# Maduino_Zero_Lorawan_Node_v2_0.net
KiCad netlist of a schematic drawn in EAGLE
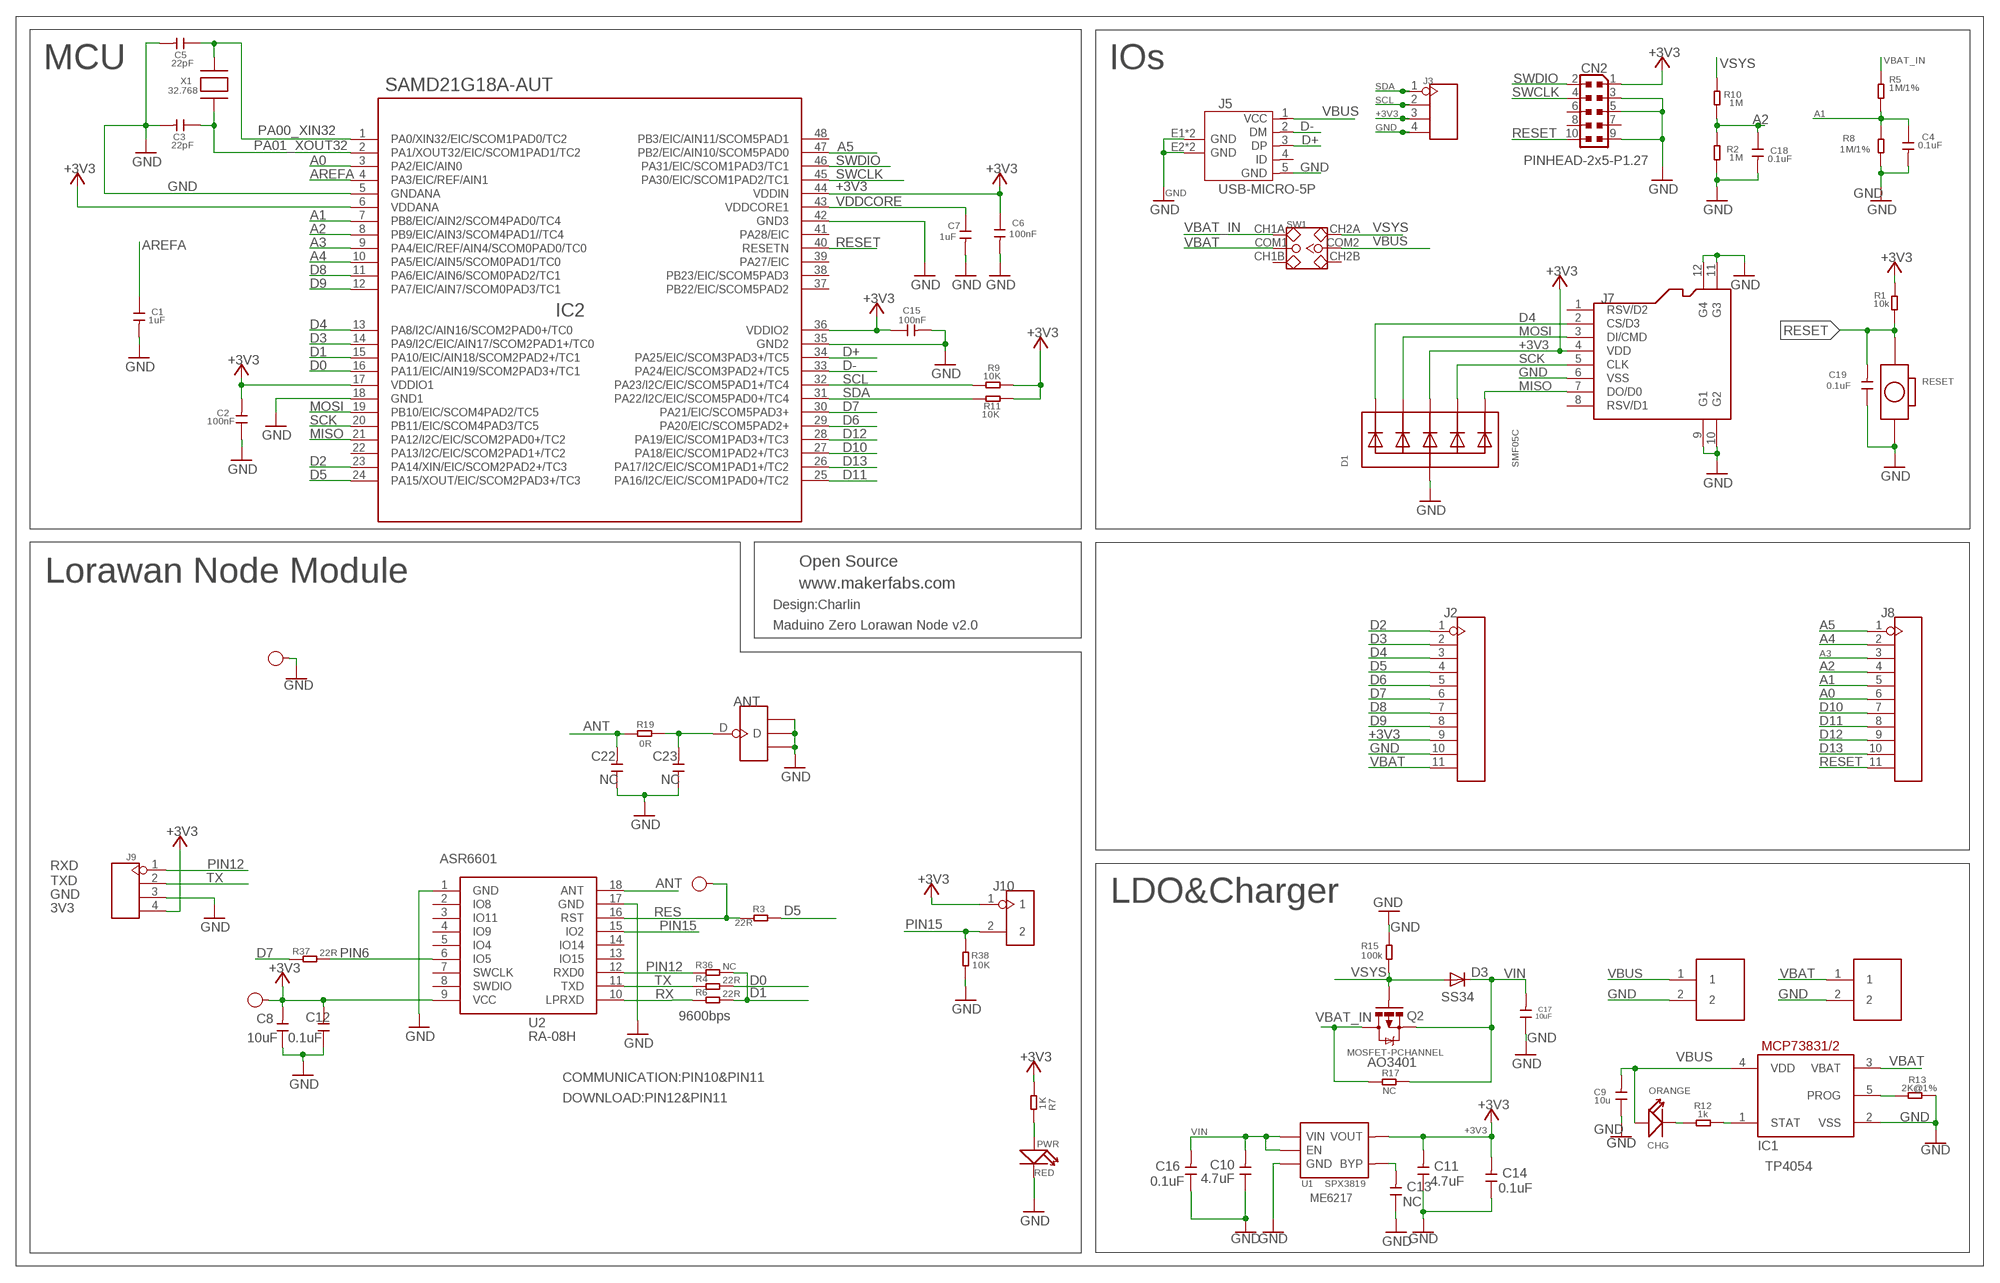
[diagram p0: schematic, sheet 1]

(export (version "E")
  (design (tool "Eeschema 10.0.6"))
  (components
    (comp (ref "3V3")
      (value "TEST-POINT'4545'")
      (footprint "eagle-import:TP-D45MIL")
      (fields (field (name "PARTNO") "DNP") (field (name "PARTNO_1") "DNP"))
      (libsource (lib "eagle-import") (part "TEST-POINT'4545'"))
    )
    (comp (ref "ANT")
      (value "ANTENNA-U-FL")
      (footprint "eagle-import:4P-U-FL")
      (libsource (lib "eagle-import") (part "ANTENNA-U-FL"))
    )
    (comp (ref "C1")
      (value "1uF")
      (footprint "eagle-import:0603")
      (libsource (lib "eagle-import") (part "C-0603"))
    )
    (comp (ref "C2")
      (value "100nF")
      (footprint "eagle-import:0603")
      (libsource (lib "eagle-import") (part "C-0603"))
    )
    (comp (ref "C3")
      (value "22pF")
      (footprint "eagle-import:0603")
      (libsource (lib "eagle-import") (part "C-0603"))
    )
    (comp (ref "C4")
      (value "0.1uF")
      (footprint "eagle-import:0603")
      (libsource (lib "eagle-import") (part "C-0603"))
    )
    (comp (ref "C5")
      (value "22pF")
      (footprint "eagle-import:0603")
      (libsource (lib "eagle-import") (part "C-0603"))
    )
    (comp (ref "C6")
      (value "100nF")
      (footprint "eagle-import:0603")
      (libsource (lib "eagle-import") (part "C-0603"))
    )
    (comp (ref "C7")
      (value "1uF")
      (footprint "eagle-import:0603")
      (libsource (lib "eagle-import") (part "C-0603"))
    )
    (comp (ref "C8")
      (value "10uF")
      (footprint "eagle-import:0603")
      (libsource (lib "eagle-import") (part "C-0603"))
    )
    (comp (ref "C9")
      (value "10u")
      (footprint "eagle-import:0603")
      (libsource (lib "eagle-import") (part "C-0603"))
    )
    (comp (ref "C10")
      (value "4.7uF")
      (footprint "eagle-import:0603")
      (libsource (lib "eagle-import") (part "C-0603"))
    )
    (comp (ref "C11")
      (value "4.7uF")
      (footprint "eagle-import:0603")
      (libsource (lib "eagle-import") (part "C-0603"))
    )
    (comp (ref "C12")
      (value "0.1uF")
      (footprint "eagle-import:0603")
      (libsource (lib "eagle-import") (part "C-0603"))
    )
    (comp (ref "C13")
      (value "NC")
      (footprint "eagle-import:0603")
      (libsource (lib "eagle-import") (part "C-0603"))
    )
    (comp (ref "C14")
      (value "0.1uF")
      (footprint "eagle-import:0603")
      (libsource (lib "eagle-import") (part "C-0603"))
    )
    (comp (ref "C15")
      (value "100nF")
      (footprint "eagle-import:0603")
      (libsource (lib "eagle-import") (part "C-0603"))
    )
    (comp (ref "C16")
      (value "0.1uF")
      (footprint "eagle-import:0603")
      (libsource (lib "eagle-import") (part "C-0603"))
    )
    (comp (ref "C17")
      (value "10uF")
      (footprint "eagle-import:0603")
      (libsource (lib "eagle-import") (part "C-0603"))
    )
    (comp (ref "C18")
      (value "0.1uF")
      (footprint "eagle-import:0603")
      (libsource (lib "eagle-import") (part "C-0603"))
    )
    (comp (ref "C19")
      (value "0.1uF")
      (footprint "eagle-import:0603")
      (libsource (lib "eagle-import") (part "C-0603"))
    )
    (comp (ref "C22")
      (value "NC")
      (footprint "eagle-import:0603")
      (libsource (lib "eagle-import") (part "C-0603"))
    )
    (comp (ref "C23")
      (value "NC")
      (footprint "eagle-import:0603")
      (libsource (lib "eagle-import") (part "C-0603"))
    )
    (comp (ref "CHG")
      (value "ORANGE")
      (footprint "eagle-import:D0603")
      (libsource (lib "eagle-import") (part "007-LED0603"))
    )
    (comp (ref "CN2")
      (value "PINHEAD-2x5-P1.27")
      (footprint "eagle-import:PINHEAD_2X05_127")
      (libsource (lib "eagle-import") (part "0171_PH127-205DF055G00AROUND-PADS"))
    )
    (comp (ref "D1")
      (value "SMF05C")
      (footprint "eagle-import:SOT363")
      (libsource (lib "eagle-import") (part "TVSARRAY_5LANE"))
    )
    (comp (ref "D3")
      (value "SS34")
      (footprint "eagle-import:DO-214AC")
      (libsource (lib "eagle-import") (part "DIODE-DO-214AC"))
    )
    (comp (ref "GND")
      (value "TEST-POINT'4545'")
      (footprint "eagle-import:TP-D45MIL")
      (fields (field (name "PARTNO") "DNP"))
      (libsource (lib "eagle-import") (part "TEST-POINT'4545'"))
    )
    (comp (ref "IC1")
      (value "MCP73831/OT")
      (footprint "eagle-import:SOT23-5L")
      (libsource (lib "eagle-import") (part "MCP73831/OT"))
    )
    (comp (ref "IC2")
      (value "SAMD21G18A-AUT")
      (footprint "eagle-import:TQFP48-7X7")
      (libsource (lib "eagle-import") (part "ATSAMD21G18A-AUT"))
    )
    (comp (ref "J1")
      (value "PH2.0-2P-90-DIP")
      (footprint "eagle-import:PH2.0-2P-90-DIP")
      (libsource (lib "eagle-import") (part "PH2.0-2P-90-DIP"))
    )
    (comp (ref "J2")
      (value "HEADER-11P-2.54")
      (footprint "eagle-import:11P-2.54")
      (libsource (lib "eagle-import") (part "HEADER-11P-2.54"))
    )
    (comp (ref "J3")
      (value "HEADER-4P-60/35MILROUND")
      (footprint "eagle-import:4P-65_35ROUND")
      (libsource (lib "eagle-import") (part "HEADER-4P-60/35MILROUND"))
    )
    (comp (ref "J5")
      (value "USB-MICRO-5P")
      (footprint "eagle-import:MICRO-USB-5P")
      (libsource (lib "eagle-import") (part "USB-MICRO-5P"))
    )
    (comp (ref "J6")
      (value "PH2.0-2P-90-DIP")
      (footprint "eagle-import:PH2.0-2P-90-DIP")
      (libsource (lib "eagle-import") (part "PH2.0-2P-90-DIP"))
    )
    (comp (ref "J7")
      (value "HOLDER-MICROSD-8P")
      (footprint "eagle-import:8P-SMD")
      (libsource (lib "eagle-import") (part "HOLDER-MICROSD-8P"))
    )
    (comp (ref "J8")
      (value "HEADER-11P-2.54")
      (footprint "eagle-import:11P-2.54")
      (libsource (lib "eagle-import") (part "HEADER-11P-2.54"))
    )
    (comp (ref "J9")
      (value "HEADER-4P-60/35MILROUND")
      (footprint "eagle-import:4P-65_35ROUND")
      (libsource (lib "eagle-import") (part "HEADER-4P-60/35MILROUND"))
    )
    (comp (ref "J10")
      (value "HEADER-2P-2.0")
      (footprint "eagle-import:2P-2.0")
      (libsource (lib "eagle-import") (part "HEADER-2P-2.0"))
    )
    (comp (ref "PWR")
      (value "RED")
      (footprint "eagle-import:LED-0603")
      (libsource (lib "eagle-import") (part "LED'0603'"))
    )
    (comp (ref "Q2")
      (value "MOSFET-PCHANNEL")
      (footprint "eagle-import:SOT23-3")
      (libsource (lib "eagle-import") (part "MOSFET-PCHANNEL"))
    )
    (comp (ref "R1")
      (value "10k")
      (footprint "eagle-import:R0603")
      (libsource (lib "eagle-import") (part "R-0603"))
    )
    (comp (ref "R2")
      (value "1M")
      (footprint "eagle-import:R0603")
      (libsource (lib "eagle-import") (part "R-0603"))
    )
    (comp (ref "R3")
      (value "22R")
      (footprint "eagle-import:R0603")
      (libsource (lib "eagle-import") (part "R-0603"))
    )
    (comp (ref "R4")
      (value "22R")
      (footprint "eagle-import:R0603")
      (libsource (lib "eagle-import") (part "R-0603"))
    )
    (comp (ref "R5")
      (value "1M/1%")
      (footprint "eagle-import:R0603")
      (libsource (lib "eagle-import") (part "R-0603"))
    )
    (comp (ref "R6")
      (value "22R")
      (footprint "eagle-import:R0603")
      (libsource (lib "eagle-import") (part "R-0603"))
    )
    (comp (ref "R7")
      (value "1K")
      (footprint "eagle-import:R0603")
      (libsource (lib "eagle-import") (part "R-0603"))
    )
    (comp (ref "R8")
      (value "1M/1%")
      (footprint "eagle-import:R0603")
      (libsource (lib "eagle-import") (part "R-0603"))
    )
    (comp (ref "R9")
      (value "10K")
      (footprint "eagle-import:R0603")
      (libsource (lib "eagle-import") (part "R-0603"))
    )
    (comp (ref "R10")
      (value "1M")
      (footprint "eagle-import:R0603")
      (libsource (lib "eagle-import") (part "R-0603"))
    )
    (comp (ref "R11")
      (value "10K")
      (footprint "eagle-import:R0603")
      (libsource (lib "eagle-import") (part "R-0603"))
    )
    (comp (ref "R12")
      (value "1k")
      (footprint "eagle-import:R0603")
      (libsource (lib "eagle-import") (part "R-0603"))
    )
    (comp (ref "R13")
      (value "2K@1%")
      (footprint "eagle-import:R0603")
      (libsource (lib "eagle-import") (part "R-0603"))
    )
    (comp (ref "R15")
      (value "100k")
      (footprint "eagle-import:R0603")
      (libsource (lib "eagle-import") (part "R-0603"))
    )
    (comp (ref "R17")
      (value "NC")
      (footprint "eagle-import:R0603")
      (libsource (lib "eagle-import") (part "R-0603"))
    )
    (comp (ref "R19")
      (value "0R")
      (footprint "eagle-import:R0603")
      (libsource (lib "eagle-import") (part "R-0603"))
    )
    (comp (ref "R36")
      (value "NC")
      (footprint "eagle-import:R0603")
      (libsource (lib "eagle-import") (part "R-0603"))
    )
    (comp (ref "R37")
      (value "22R")
      (footprint "eagle-import:R0603")
      (libsource (lib "eagle-import") (part "R-0603"))
    )
    (comp (ref "R38")
      (value "10K")
      (footprint "eagle-import:R0603")
      (libsource (lib "eagle-import") (part "R-0603"))
    )
    (comp (ref "RESET")
      (value "BOTTON-2P-90D")
      (footprint "eagle-import:2P-7.62X3.56-90D")
      (libsource (lib "eagle-import") (part "BOTTON-2P-90D"))
    )
    (comp (ref "RST")
      (value "TEST-POINT'4545'")
      (footprint "eagle-import:TP-D45MIL")
      (fields (field (name "PARTNO") "DNP") (field (name "PARTNO_1") "DNP"))
      (libsource (lib "eagle-import") (part "TEST-POINT'4545'"))
    )
    (comp (ref "SW1")
      (value "SWITCH-2CH-6P")
      (footprint "eagle-import:6P-2CH-2.54-7.6X3.0")
      (libsource (lib "eagle-import") (part "SWITCH-2CH-6P"))
    )
    (comp (ref "U1")
      (value "SPX3819")
      (footprint "eagle-import:SOT23-5")
      (libsource (lib "eagle-import") (part "SPX3819"))
    )
    (comp (ref "U2")
      (value "RA-08H")
      (footprint "eagle-import:RA-08H")
      (libsource (lib "eagle-import") (part "RA-08H"))
    )
    (comp (ref "X1")
      (value "32.768")
      (footprint "eagle-import:XTAL3215")
      (libsource (lib "eagle-import") (part "XTAL-3.2X1.5"))
    )
  )
  (nets
    (net (code "1") (name "+3V3") (class "Default")
      (node (ref "3V3") (pin "T") (pinfunction "T_T") (pintype "bidirectional"))
      (node (ref "C11") (pin "2") (pinfunction "2_2") (pintype "passive"))
      (node (ref "C12") (pin "2") (pinfunction "2_2") (pintype "passive"))
      (node (ref "C14") (pin "2") (pinfunction "2_2") (pintype "passive"))
      (node (ref "C15") (pin "1") (pinfunction "1_1") (pintype "passive"))
      (node (ref "C2") (pin "2") (pinfunction "2_2") (pintype "passive"))
      (node (ref "C6") (pin "1") (pinfunction "1_1") (pintype "passive"))
      (node (ref "C8") (pin "2") (pinfunction "2_2") (pintype "passive"))
      (node (ref "CN2") (pin "1") (pinfunction "1_1") (pintype "passive"))
      (node (ref "D1") (pin "4") (pinfunction "C3_4") (pintype "passive"))
      (node (ref "IC2") (pin "17") (pinfunction "VDDIO1_17") (pintype "power_in"))
      (node (ref "IC2") (pin "36") (pinfunction "VDDIO2_36") (pintype "power_in"))
      (node (ref "IC2") (pin "44") (pinfunction "VDDIN_44") (pintype "power_in"))
      (node (ref "IC2") (pin "6") (pinfunction "VDDANA_6") (pintype "power_in"))
      (node (ref "J10") (pin "1") (pinfunction "1_1") (pintype "bidirectional"))
      (node (ref "J2") (pin "9") (pinfunction "9_9") (pintype "bidirectional"))
      (node (ref "J3") (pin "3") (pinfunction "P$3_3") (pintype "bidirectional"))
      (node (ref "J7") (pin "4") (pinfunction "VDD_4") (pintype "bidirectional"))
      (node (ref "J9") (pin "4") (pinfunction "P$4_4") (pintype "bidirectional"))
      (node (ref "R1") (pin "2") (pinfunction "2_2") (pintype "passive"))
      (node (ref "R11") (pin "2") (pinfunction "2_2") (pintype "passive"))
      (node (ref "R7") (pin "1") (pinfunction "1_1") (pintype "passive"))
      (node (ref "R9") (pin "2") (pinfunction "2_2") (pintype "passive"))
      (node (ref "U1") (pin "5") (pinfunction "VOUT_5") (pintype "bidirectional"))
      (node (ref "U2") (pin "9") (pinfunction "VCC_9") (pintype "bidirectional"))
    )
    (net (code "2") (name "/A0") (class "Default")
      (node (ref "IC2") (pin "3") (pinfunction "PA2/EIC/AIN0_3") (pintype "bidirectional"))
      (node (ref "J8") (pin "6") (pinfunction "6_6") (pintype "bidirectional"))
    )
    (net (code "3") (name "/A1") (class "Default")
      (node (ref "C4") (pin "1") (pinfunction "1_1") (pintype "passive"))
      (node (ref "IC2") (pin "7") (pinfunction "PB8/EIC/AIN2/SCOM4PAD0/TC4_7") (pintype "bidirectional"))
      (node (ref "J8") (pin "5") (pinfunction "5_5") (pintype "bidirectional"))
      (node (ref "R5") (pin "1") (pinfunction "1_1") (pintype "passive"))
      (node (ref "R8") (pin "2") (pinfunction "2_2") (pintype "passive"))
    )
    (net (code "4") (name "/A2") (class "Default")
      (node (ref "C18") (pin "1") (pinfunction "1_1") (pintype "passive"))
      (node (ref "IC2") (pin "8") (pinfunction "PB9/EIC/AIN3/SCOM4PAD1//TC4_8") (pintype "bidirectional"))
      (node (ref "J8") (pin "4") (pinfunction "4_4") (pintype "bidirectional"))
      (node (ref "R10") (pin "1") (pinfunction "1_1") (pintype "passive"))
      (node (ref "R2") (pin "2") (pinfunction "2_2") (pintype "passive"))
    )
    (net (code "5") (name "/A3") (class "Default")
      (node (ref "IC2") (pin "9") (pinfunction "PA4/EIC/REF/AIN4/SCOM0PAD0/TC0_9") (pintype "bidirectional"))
      (node (ref "J8") (pin "3") (pinfunction "3_3") (pintype "bidirectional"))
    )
    (net (code "6") (name "/A4") (class "Default")
      (node (ref "IC2") (pin "10") (pinfunction "PA5/EIC/AIN5/SCOM0PAD1/TC0_10") (pintype "bidirectional"))
      (node (ref "J8") (pin "2") (pinfunction "2_2") (pintype "bidirectional"))
    )
    (net (code "7") (name "/A5") (class "Default")
      (node (ref "IC2") (pin "47") (pinfunction "PB2/EIC/AIN10/SCOM5PAD0_47") (pintype "bidirectional"))
      (node (ref "J8") (pin "1") (pinfunction "1_1") (pintype "bidirectional"))
    )
    (net (code "8") (name "/ANT") (class "Default")
      (node (ref "C22") (pin "2") (pinfunction "2_2") (pintype "passive"))
      (node (ref "R19") (pin "1") (pinfunction "1_1") (pintype "passive"))
      (node (ref "U2") (pin "18") (pinfunction "ANT_18") (pintype "bidirectional"))
    )
    (net (code "9") (name "/AREFA") (class "Default")
      (node (ref "C1") (pin "1") (pinfunction "1_1") (pintype "passive"))
      (node (ref "IC2") (pin "4") (pinfunction "PA3/EIC/REF/AIN1_4") (pintype "bidirectional"))
    )
    (net (code "10") (name "/D+") (class "Default")
      (node (ref "IC2") (pin "34") (pinfunction "PA25/EIC/SCOM3PAD3+/TC5_34") (pintype "bidirectional"))
      (node (ref "J5") (pin "3") (pinfunction "DP_3") (pintype "bidirectional"))
    )
    (net (code "11") (name "/D-") (class "Default")
      (node (ref "IC2") (pin "33") (pinfunction "PA24/EIC/SCOM3PAD2+/TC5_33") (pintype "bidirectional"))
      (node (ref "J5") (pin "2") (pinfunction "DM_2") (pintype "bidirectional"))
    )
    (net (code "12") (name "/D0") (class "Default")
      (node (ref "IC2") (pin "16") (pinfunction "PA11/EIC/AIN19/SCOM2PAD3+/TC1_16") (pintype "bidirectional"))
      (node (ref "R4") (pin "2") (pinfunction "2_2") (pintype "passive"))
    )
    (net (code "13") (name "/D1") (class "Default")
      (node (ref "IC2") (pin "15") (pinfunction "PA10/EIC/AIN18/SCOM2PAD2+/TC1_15") (pintype "bidirectional"))
      (node (ref "R36") (pin "2") (pinfunction "2_2") (pintype "passive"))
      (node (ref "R6") (pin "2") (pinfunction "2_2") (pintype "passive"))
    )
    (net (code "14") (name "/D2") (class "Default")
      (node (ref "IC2") (pin "23") (pinfunction "PA14/XIN/EIC/SCOM2PAD2+/TC3_23") (pintype "bidirectional"))
      (node (ref "J2") (pin "1") (pinfunction "1_1") (pintype "bidirectional"))
    )
    (net (code "15") (name "/D3") (class "Default")
      (node (ref "IC2") (pin "14") (pinfunction "PA9/I2C/EIC/AIN17/SCOM2PAD1+/TC0_14") (pintype "bidirectional"))
      (node (ref "J2") (pin "2") (pinfunction "2_2") (pintype "bidirectional"))
    )
    (net (code "16") (name "/D4") (class "Default")
      (node (ref "D1") (pin "1") (pinfunction "C1_1") (pintype "passive"))
      (node (ref "IC2") (pin "13") (pinfunction "PA8/I2C/AIN16/SCOM2PAD0+/TC0_13") (pintype "bidirectional"))
      (node (ref "J2") (pin "3") (pinfunction "3_3") (pintype "bidirectional"))
      (node (ref "J7") (pin "2") (pinfunction "CS/D3_2") (pintype "bidirectional"))
    )
    (net (code "17") (name "/D5") (class "Default")
      (node (ref "IC2") (pin "24") (pinfunction "PA15/XOUT/EIC/SCOM2PAD3+/TC3_24") (pintype "bidirectional"))
      (node (ref "J2") (pin "4") (pinfunction "4_4") (pintype "bidirectional"))
      (node (ref "R3") (pin "2") (pinfunction "2_2") (pintype "passive"))
    )
    (net (code "18") (name "/D6") (class "Default")
      (node (ref "IC2") (pin "29") (pinfunction "PA20/EIC/SCOM5PAD2+_29") (pintype "bidirectional"))
      (node (ref "J2") (pin "5") (pinfunction "5_5") (pintype "bidirectional"))
    )
    (net (code "19") (name "/D7") (class "Default")
      (node (ref "IC2") (pin "30") (pinfunction "PA21/EIC/SCOM5PAD3+_30") (pintype "bidirectional"))
      (node (ref "J2") (pin "6") (pinfunction "6_6") (pintype "bidirectional"))
      (node (ref "R37") (pin "1") (pinfunction "1_1") (pintype "passive"))
    )
    (net (code "20") (name "/D8") (class "Default")
      (node (ref "IC2") (pin "11") (pinfunction "PA6/EIC/AIN6/SCOM0PAD2/TC1_11") (pintype "bidirectional"))
      (node (ref "J2") (pin "7") (pinfunction "7_7") (pintype "bidirectional"))
    )
    (net (code "21") (name "/D9") (class "Default")
      (node (ref "IC2") (pin "12") (pinfunction "PA7/EIC/AIN7/SCOM0PAD3/TC1_12") (pintype "bidirectional"))
      (node (ref "J2") (pin "8") (pinfunction "8_8") (pintype "bidirectional"))
    )
    (net (code "22") (name "/D10") (class "Default")
      (node (ref "IC2") (pin "27") (pinfunction "PA18/EIC/SCOM1PAD2+/TC3_27") (pintype "bidirectional"))
      (node (ref "J8") (pin "7") (pinfunction "7_7") (pintype "bidirectional"))
    )
    (net (code "23") (name "/D11") (class "Default")
      (node (ref "IC2") (pin "25") (pinfunction "PA16/I2C/EIC/SCOM1PAD0+/TC2_25") (pintype "bidirectional"))
      (node (ref "J8") (pin "8") (pinfunction "8_8") (pintype "bidirectional"))
    )
    (net (code "24") (name "/D12") (class "Default")
      (node (ref "IC2") (pin "28") (pinfunction "PA19/EIC/SCOM1PAD3+/TC3_28") (pintype "bidirectional"))
      (node (ref "J8") (pin "9") (pinfunction "9_9") (pintype "bidirectional"))
    )
    (net (code "25") (name "/D13") (class "Default")
      (node (ref "IC2") (pin "26") (pinfunction "PA17/I2C/EIC/SCOM1PAD1+/TC2_26") (pintype "bidirectional"))
      (node (ref "J8") (pin "10") (pinfunction "10_10") (pintype "bidirectional"))
    )
    (net (code "26") (name "/MISO") (class "Default")
      (node (ref "D1") (pin "6") (pinfunction "C5_6") (pintype "passive"))
      (node (ref "IC2") (pin "21") (pinfunction "PA12/I2C/EIC/SCOM2PAD0+/TC2_21") (pintype "bidirectional"))
      (node (ref "J7") (pin "7") (pinfunction "DO/D0_7") (pintype "bidirectional"))
    )
    (net (code "27") (name "/MOSI") (class "Default")
      (node (ref "D1") (pin "3") (pinfunction "C2_3") (pintype "passive"))
      (node (ref "IC2") (pin "19") (pinfunction "PB10/EIC/SCOM4PAD2/TC5_19") (pintype "bidirectional"))
      (node (ref "J7") (pin "3") (pinfunction "DI/CMD_3") (pintype "bidirectional"))
    )
    (net (code "28") (name "/PA00_XIN32") (class "Default")
      (node (ref "C5") (pin "1") (pinfunction "1_1") (pintype "passive"))
      (node (ref "IC2") (pin "1") (pinfunction "PA0/XIN32/EIC/SCOM1PAD0/TC2_1") (pintype "bidirectional"))
      (node (ref "X1") (pin "P$2") (pinfunction "P$2_P$2") (pintype "bidirectional"))
    )
    (net (code "29") (name "/PA01_XOUT32") (class "Default")
      (node (ref "C3") (pin "1") (pinfunction "1_1") (pintype "passive"))
      (node (ref "IC2") (pin "2") (pinfunction "PA1/XOUT32/EIC/SCOM1PAD1/TC2_2") (pintype "bidirectional"))
      (node (ref "X1") (pin "P$1") (pinfunction "P$1_P$1") (pintype "bidirectional"))
    )
    (net (code "30") (name "/PIN6") (class "Default")
      (node (ref "R37") (pin "2") (pinfunction "2_2") (pintype "passive"))
      (node (ref "U2") (pin "6") (pinfunction "IO5_6") (pintype "bidirectional"))
    )
    (net (code "31") (name "/PIN12") (class "Default")
      (node (ref "J9") (pin "1") (pinfunction "P$1_1") (pintype "bidirectional"))
      (node (ref "R36") (pin "1") (pinfunction "1_1") (pintype "passive"))
      (node (ref "U2") (pin "12") (pinfunction "RXD0_12") (pintype "bidirectional"))
    )
    (net (code "32") (name "/PIN15") (class "Default")
      (node (ref "J10") (pin "2") (pinfunction "2_2") (pintype "bidirectional"))
      (node (ref "R38") (pin "1") (pinfunction "1_1") (pintype "passive"))
      (node (ref "U2") (pin "15") (pinfunction "IO2_15") (pintype "bidirectional"))
    )
    (net (code "33") (name "/RES") (class "Default")
      (node (ref "R3") (pin "1") (pinfunction "1_1") (pintype "passive"))
      (node (ref "RST") (pin "T") (pinfunction "T_T") (pintype "bidirectional"))
      (node (ref "U2") (pin "16") (pinfunction "RST_16") (pintype "bidirectional"))
    )
    (net (code "34") (name "/RX") (class "Default")
      (node (ref "R6") (pin "1") (pinfunction "1_1") (pintype "passive"))
      (node (ref "U2") (pin "10") (pinfunction "LPRXD_10") (pintype "bidirectional"))
    )
    (net (code "35") (name "/SCK") (class "Default")
      (node (ref "D1") (pin "5") (pinfunction "C4_5") (pintype "passive"))
      (node (ref "IC2") (pin "20") (pinfunction "PB11/EIC/SCOM4PAD3/TC5_20") (pintype "bidirectional"))
      (node (ref "J7") (pin "5") (pinfunction "CLK_5") (pintype "bidirectional"))
    )
    (net (code "36") (name "/SCL") (class "Default")
      (node (ref "IC2") (pin "32") (pinfunction "PA23/I2C/EIC/SCOM5PAD1+/TC4_32") (pintype "bidirectional"))
      (node (ref "J3") (pin "2") (pinfunction "P$2_2") (pintype "bidirectional"))
      (node (ref "R9") (pin "1") (pinfunction "1_1") (pintype "passive"))
    )
    (net (code "37") (name "/SDA") (class "Default")
      (node (ref "IC2") (pin "31") (pinfunction "PA22/I2C/EIC/SCOM5PAD0+/TC4_31") (pintype "bidirectional"))
      (node (ref "J3") (pin "1") (pinfunction "P$1_1") (pintype "bidirectional"))
      (node (ref "R11") (pin "1") (pinfunction "1_1") (pintype "passive"))
    )
    (net (code "38") (name "/SWCLK") (class "Default")
      (node (ref "CN2") (pin "4") (pinfunction "4_4") (pintype "passive"))
      (node (ref "IC2") (pin "45") (pinfunction "PA30/EIC/SCOM1PAD2/TC1_45") (pintype "bidirectional"))
    )
    (net (code "39") (name "/SWDIO") (class "Default")
      (node (ref "CN2") (pin "2") (pinfunction "2_2") (pintype "passive"))
      (node (ref "IC2") (pin "46") (pinfunction "PA31/EIC/SCOM1PAD3/TC1_46") (pintype "bidirectional"))
    )
    (net (code "40") (name "/TX") (class "Default")
      (node (ref "J9") (pin "2") (pinfunction "P$2_2") (pintype "bidirectional"))
      (node (ref "R4") (pin "1") (pinfunction "1_1") (pintype "passive"))
      (node (ref "U2") (pin "11") (pinfunction "TXD_11") (pintype "bidirectional"))
    )
    (net (code "41") (name "/VBAT") (class "Default")
      (node (ref "IC1") (pin "3") (pinfunction "VBAT_3") (pintype "bidirectional"))
      (node (ref "J2") (pin "11") (pinfunction "11_11") (pintype "bidirectional"))
      (node (ref "J6") (pin "1") (pinfunction "1_1") (pintype "bidirectional"))
      (node (ref "SW1") (pin "COM1") (pinfunction "COM1_COM1") (pintype "bidirectional"))
    )
    (net (code "42") (name "/VBAT_IN") (class "Default")
      (node (ref "Q2") (pin "3") (pinfunction "D_3") (pintype "passive"))
      (node (ref "R17") (pin "1") (pinfunction "1_1") (pintype "passive"))
      (node (ref "R5") (pin "2") (pinfunction "2_2") (pintype "passive"))
      (node (ref "SW1") (pin "CH1A") (pinfunction "CH1A_CH1A") (pintype "bidirectional"))
    )
    (net (code "43") (name "/VBUS") (class "Default")
      (node (ref "C9") (pin "2") (pinfunction "2_2") (pintype "passive"))
      (node (ref "CHG") (pin "+") (pinfunction "+_+") (pintype "passive"))
      (node (ref "IC1") (pin "4") (pinfunction "VDD_4") (pintype "power_in"))
      (node (ref "J1") (pin "1") (pinfunction "1_1") (pintype "bidirectional"))
      (node (ref "J5") (pin "1") (pinfunction "VCC_1") (pintype "bidirectional"))
      (node (ref "SW1") (pin "COM2") (pinfunction "COM2_COM2") (pintype "bidirectional"))
    )
    (net (code "44") (name "/VDDCORE") (class "Default")
      (node (ref "C7") (pin "1") (pinfunction "1_1") (pintype "passive"))
      (node (ref "IC2") (pin "43") (pinfunction "VDDCORE1_43") (pintype "input"))
    )
    (net (code "45") (name "/VIN") (class "Default")
      (node (ref "C10") (pin "2") (pinfunction "2_2") (pintype "passive"))
      (node (ref "C16") (pin "2") (pinfunction "2_2") (pintype "passive"))
      (node (ref "C17") (pin "2") (pinfunction "2_2") (pintype "passive"))
      (node (ref "D3") (pin "C") (pinfunction "C_C") (pintype "passive"))
      (node (ref "Q2") (pin "2") (pinfunction "S_2") (pintype "passive"))
      (node (ref "R17") (pin "2") (pinfunction "2_2") (pintype "passive"))
      (node (ref "U1") (pin "1") (pinfunction "VIN_1") (pintype "bidirectional"))
      (node (ref "U1") (pin "3") (pinfunction "EN_3") (pintype "bidirectional"))
    )
    (net (code "46") (name "/VSYS") (class "Default")
      (node (ref "D3") (pin "A") (pinfunction "A_A") (pintype "passive"))
      (node (ref "Q2") (pin "1") (pinfunction "G_1") (pintype "passive"))
      (node (ref "R10") (pin "2") (pinfunction "2_2") (pintype "passive"))
      (node (ref "R15") (pin "1") (pinfunction "1_1") (pintype "passive"))
      (node (ref "SW1") (pin "CH2A") (pinfunction "CH2A_CH2A") (pintype "bidirectional"))
    )
    (net (code "47") (name "GND") (class "Default")
      (node (ref "ANT") (pin "GND1") (pinfunction "GND1_GND1") (pintype "bidirectional"))
      (node (ref "ANT") (pin "GND2") (pinfunction "GND2_GND2") (pintype "bidirectional"))
      (node (ref "ANT") (pin "GND3") (pinfunction "GND3_GND3") (pintype "bidirectional"))
      (node (ref "C1") (pin "2") (pinfunction "2_2") (pintype "passive"))
      (node (ref "C10") (pin "1") (pinfunction "1_1") (pintype "passive"))
      (node (ref "C11") (pin "1") (pinfunction "1_1") (pintype "passive"))
      (node (ref "C12") (pin "1") (pinfunction "1_1") (pintype "passive"))
      (node (ref "C13") (pin "1") (pinfunction "1_1") (pintype "passive"))
      (node (ref "C14") (pin "1") (pinfunction "1_1") (pintype "passive"))
      (node (ref "C15") (pin "2") (pinfunction "2_2") (pintype "passive"))
      (node (ref "C16") (pin "1") (pinfunction "1_1") (pintype "passive"))
      (node (ref "C17") (pin "1") (pinfunction "1_1") (pintype "passive"))
      (node (ref "C18") (pin "2") (pinfunction "2_2") (pintype "passive"))
      (node (ref "C19") (pin "1") (pinfunction "1_1") (pintype "passive"))
      (node (ref "C2") (pin "1") (pinfunction "1_1") (pintype "passive"))
      (node (ref "C22") (pin "1") (pinfunction "1_1") (pintype "passive"))
      (node (ref "C23") (pin "1") (pinfunction "1_1") (pintype "passive"))
      (node (ref "C3") (pin "2") (pinfunction "2_2") (pintype "passive"))
      (node (ref "C4") (pin "2") (pinfunction "2_2") (pintype "passive"))
      (node (ref "C5") (pin "2") (pinfunction "2_2") (pintype "passive"))
      (node (ref "C6") (pin "2") (pinfunction "2_2") (pintype "passive"))
      (node (ref "C7") (pin "2") (pinfunction "2_2") (pintype "passive"))
      (node (ref "C8") (pin "1") (pinfunction "1_1") (pintype "passive"))
      (node (ref "C9") (pin "1") (pinfunction "1_1") (pintype "passive"))
      (node (ref "CN2") (pin "3") (pinfunction "3_3") (pintype "passive"))
      (node (ref "CN2") (pin "5") (pinfunction "5_5") (pintype "passive"))
      (node (ref "CN2") (pin "9") (pinfunction "9_9") (pintype "passive"))
      (node (ref "D1") (pin "2") (pinfunction "A_2") (pintype "passive"))
      (node (ref "GND") (pin "T") (pinfunction "T_T") (pintype "bidirectional"))
      (node (ref "IC1") (pin "2") (pinfunction "VSS_2") (pintype "power_in"))
      (node (ref "IC2") (pin "18") (pinfunction "GND1_18") (pintype "power_in"))
      (node (ref "IC2") (pin "35") (pinfunction "GND2_35") (pintype "power_in"))
      (node (ref "IC2") (pin "42") (pinfunction "GND3_42") (pintype "power_in"))
      (node (ref "IC2") (pin "5") (pinfunction "GNDANA_5") (pintype "power_in"))
      (node (ref "J1") (pin "2") (pinfunction "2_2") (pintype "bidirectional"))
      (node (ref "J2") (pin "10") (pinfunction "10_10") (pintype "bidirectional"))
      (node (ref "J3") (pin "4") (pinfunction "P$4_4") (pintype "bidirectional"))
      (node (ref "J5") (pin "5") (pinfunction "GND_5") (pintype "bidirectional"))
      (node (ref "J5") (pin "E1") (pinfunction "GND_E1") (pintype "bidirectional"))
      (node (ref "J5") (pin "E2") (pinfunction "GND_E2") (pintype "bidirectional"))
      (node (ref "J5") (pin "P1") (pinfunction "GND_P1") (pintype "bidirectional"))
      (node (ref "J5") (pin "P2") (pinfunction "GND_P2") (pintype "bidirectional"))
      (node (ref "J6") (pin "2") (pinfunction "2_2") (pintype "bidirectional"))
      (node (ref "J7") (pin "10") (pinfunction "G2_10") (pintype "bidirectional"))
      (node (ref "J7") (pin "11") (pinfunction "G3_11") (pintype "bidirectional"))
      (node (ref "J7") (pin "12") (pinfunction "G4_12") (pintype "bidirectional"))
      (node (ref "J7") (pin "6") (pinfunction "VSS_6") (pintype "bidirectional"))
      (node (ref "J7") (pin "9") (pinfunction "G1_9") (pintype "bidirectional"))
      (node (ref "J9") (pin "3") (pinfunction "P$3_3") (pintype "bidirectional"))
      (node (ref "PWR") (pin "-") (pinfunction "-_-") (pintype "passive"))
      (node (ref "R13") (pin "2") (pinfunction "2_2") (pintype "passive"))
      (node (ref "R15") (pin "2") (pinfunction "2_2") (pintype "passive"))
      (node (ref "R2") (pin "1") (pinfunction "1_1") (pintype "passive"))
      (node (ref "R38") (pin "2") (pinfunction "2_2") (pintype "passive"))
      (node (ref "R8") (pin "1") (pinfunction "1_1") (pintype "passive"))
      (node (ref "RESET") (pin "P$2") (pinfunction "2_P$2") (pintype "bidirectional"))
      (node (ref "U1") (pin "2") (pinfunction "GND_2") (pintype "bidirectional"))
      (node (ref "U2") (pin "1") (pinfunction "GND_1") (pintype "bidirectional"))
      (node (ref "U2") (pin "17") (pinfunction "GND_17") (pintype "bidirectional"))
    )
    (net (code "48") (name "Net-(ANT-PadD)") (class "Default")
      (node (ref "ANT") (pin "D") (pinfunction "D_D") (pintype "bidirectional"))
      (node (ref "C23") (pin "2") (pinfunction "2_2") (pintype "passive"))
      (node (ref "R19") (pin "2") (pinfunction "2_2") (pintype "passive"))
    )
    (net (code "49") (name "Net-(CHG-Pad-)") (class "Default")
      (node (ref "CHG") (pin "-") (pinfunction "-_-") (pintype "passive"))
      (node (ref "R12") (pin "1") (pinfunction "1_1") (pintype "passive"))
    )
    (net (code "50") (name "Net-(IC1-PROG)") (class "Default")
      (node (ref "IC1") (pin "5") (pinfunction "PROG_5") (pintype "input"))
      (node (ref "R13") (pin "1") (pinfunction "1_1") (pintype "passive"))
    )
    (net (code "51") (name "Net-(IC1-STAT)") (class "Default")
      (node (ref "IC1") (pin "1") (pinfunction "STAT_1") (pintype "output"))
      (node (ref "R12") (pin "2") (pinfunction "2_2") (pintype "passive"))
    )
    (net (code "52") (name "Net-(PWR-Pad+)") (class "Default")
      (node (ref "PWR") (pin "+") (pinfunction "+_+") (pintype "passive"))
      (node (ref "R7") (pin "2") (pinfunction "2_2") (pintype "passive"))
    )
    (net (code "53") (name "Net-(U1-BYP)") (class "Default")
      (node (ref "C13") (pin "2") (pinfunction "2_2") (pintype "passive"))
      (node (ref "U1") (pin "4") (pinfunction "BYP_4") (pintype "bidirectional"))
    )
    (net (code "54") (name "RESET") (class "Default")
      (node (ref "C19") (pin "2") (pinfunction "2_2") (pintype "passive"))
      (node (ref "CN2") (pin "10") (pinfunction "10_10") (pintype "passive"))
      (node (ref "IC2") (pin "40") (pinfunction "RESETN_40") (pintype "bidirectional"))
      (node (ref "J8") (pin "11") (pinfunction "11_11") (pintype "bidirectional"))
      (node (ref "R1") (pin "1") (pinfunction "1_1") (pintype "passive"))
      (node (ref "RESET") (pin "P$1") (pinfunction "1_P$1") (pintype "bidirectional"))
    )
    (net (code "55") (name "unconnected-(CN2-Pad6)") (class "Default")
      (node (ref "CN2") (pin "6") (pinfunction "6_6") (pintype "passive"))
    )
    (net (code "56") (name "unconnected-(CN2-Pad7)") (class "Default")
      (node (ref "CN2") (pin "7") (pinfunction "7_7") (pintype "passive"))
    )
    (net (code "57") (name "unconnected-(CN2-Pad8)") (class "Default")
      (node (ref "CN2") (pin "8") (pinfunction "8_8") (pintype "passive"))
    )
    (net (code "58") (name "unconnected-(IC2-PA13{slash}I2C{slash}EIC{slash}SCOM2PAD1+{slash}TC2-Pad22)") (class "Default")
      (node (ref "IC2") (pin "22") (pinfunction "PA13/I2C/EIC/SCOM2PAD1+/TC2_22") (pintype "bidirectional"))
    )
    (net (code "59") (name "unconnected-(IC2-PA27{slash}EIC-Pad39)") (class "Default")
      (node (ref "IC2") (pin "39") (pinfunction "PA27/EIC_39") (pintype "bidirectional"))
    )
    (net (code "60") (name "unconnected-(IC2-PA28{slash}EIC-Pad41)") (class "Default")
      (node (ref "IC2") (pin "41") (pinfunction "PA28/EIC_41") (pintype "bidirectional"))
    )
    (net (code "61") (name "unconnected-(IC2-PB3{slash}EIC{slash}AIN11{slash}SCOM5PAD1-Pad48)") (class "Default")
      (node (ref "IC2") (pin "48") (pinfunction "PB3/EIC/AIN11/SCOM5PAD1_48") (pintype "bidirectional"))
    )
    (net (code "62") (name "unconnected-(IC2-PB22{slash}EIC{slash}SCOM5PAD2-Pad37)") (class "Default")
      (node (ref "IC2") (pin "37") (pinfunction "PB22/EIC/SCOM5PAD2_37") (pintype "bidirectional"))
    )
    (net (code "63") (name "unconnected-(IC2-PB23{slash}EIC{slash}SCOM5PAD3-Pad38)") (class "Default")
      (node (ref "IC2") (pin "38") (pinfunction "PB23/EIC/SCOM5PAD3_38") (pintype "bidirectional"))
    )
    (net (code "64") (name "unconnected-(J5-ID-Pad4)") (class "Default")
      (node (ref "J5") (pin "4") (pinfunction "ID_4") (pintype "bidirectional"))
    )
    (net (code "65") (name "unconnected-(J7-RSV{slash}D1-Pad8)") (class "Default")
      (node (ref "J7") (pin "8") (pinfunction "RSV/D1_8") (pintype "bidirectional"))
    )
    (net (code "66") (name "unconnected-(J7-RSV{slash}D2-Pad1)") (class "Default")
      (node (ref "J7") (pin "1") (pinfunction "RSV/D2_1") (pintype "bidirectional"))
    )
    (net (code "67") (name "unconnected-(SW1-PadCH1B)") (class "Default")
      (node (ref "SW1") (pin "CH1B") (pinfunction "CH1B_CH1B") (pintype "bidirectional"))
    )
    (net (code "68") (name "unconnected-(SW1-PadCH2B)") (class "Default")
      (node (ref "SW1") (pin "CH2B") (pinfunction "CH2B_CH2B") (pintype "bidirectional"))
    )
    (net (code "69") (name "unconnected-(U2-IO4-Pad5)") (class "Default")
      (node (ref "U2") (pin "5") (pinfunction "IO4_5") (pintype "bidirectional"))
    )
    (net (code "70") (name "unconnected-(U2-IO8-Pad2)") (class "Default")
      (node (ref "U2") (pin "2") (pinfunction "IO8_2") (pintype "bidirectional"))
    )
    (net (code "71") (name "unconnected-(U2-IO9-Pad4)") (class "Default")
      (node (ref "U2") (pin "4") (pinfunction "IO9_4") (pintype "bidirectional"))
    )
    (net (code "72") (name "unconnected-(U2-IO11-Pad3)") (class "Default")
      (node (ref "U2") (pin "3") (pinfunction "IO11_3") (pintype "bidirectional"))
    )
    (net (code "73") (name "unconnected-(U2-IO14-Pad14)") (class "Default")
      (node (ref "U2") (pin "14") (pinfunction "IO14_14") (pintype "bidirectional"))
    )
    (net (code "74") (name "unconnected-(U2-IO15-Pad13)") (class "Default")
      (node (ref "U2") (pin "13") (pinfunction "IO15_13") (pintype "bidirectional"))
    )
    (net (code "75") (name "unconnected-(U2-SWCLK-Pad7)") (class "Default")
      (node (ref "U2") (pin "7") (pinfunction "SWCLK_7") (pintype "bidirectional"))
    )
    (net (code "76") (name "unconnected-(U2-SWDIO-Pad8)") (class "Default")
      (node (ref "U2") (pin "8") (pinfunction "SWDIO_8") (pintype "bidirectional"))
    )
  )
)
